# Nuio_Left_Keyboard_Rev_H_MCU.net
KiCad netlist of a schematic drawn in Altium Designer
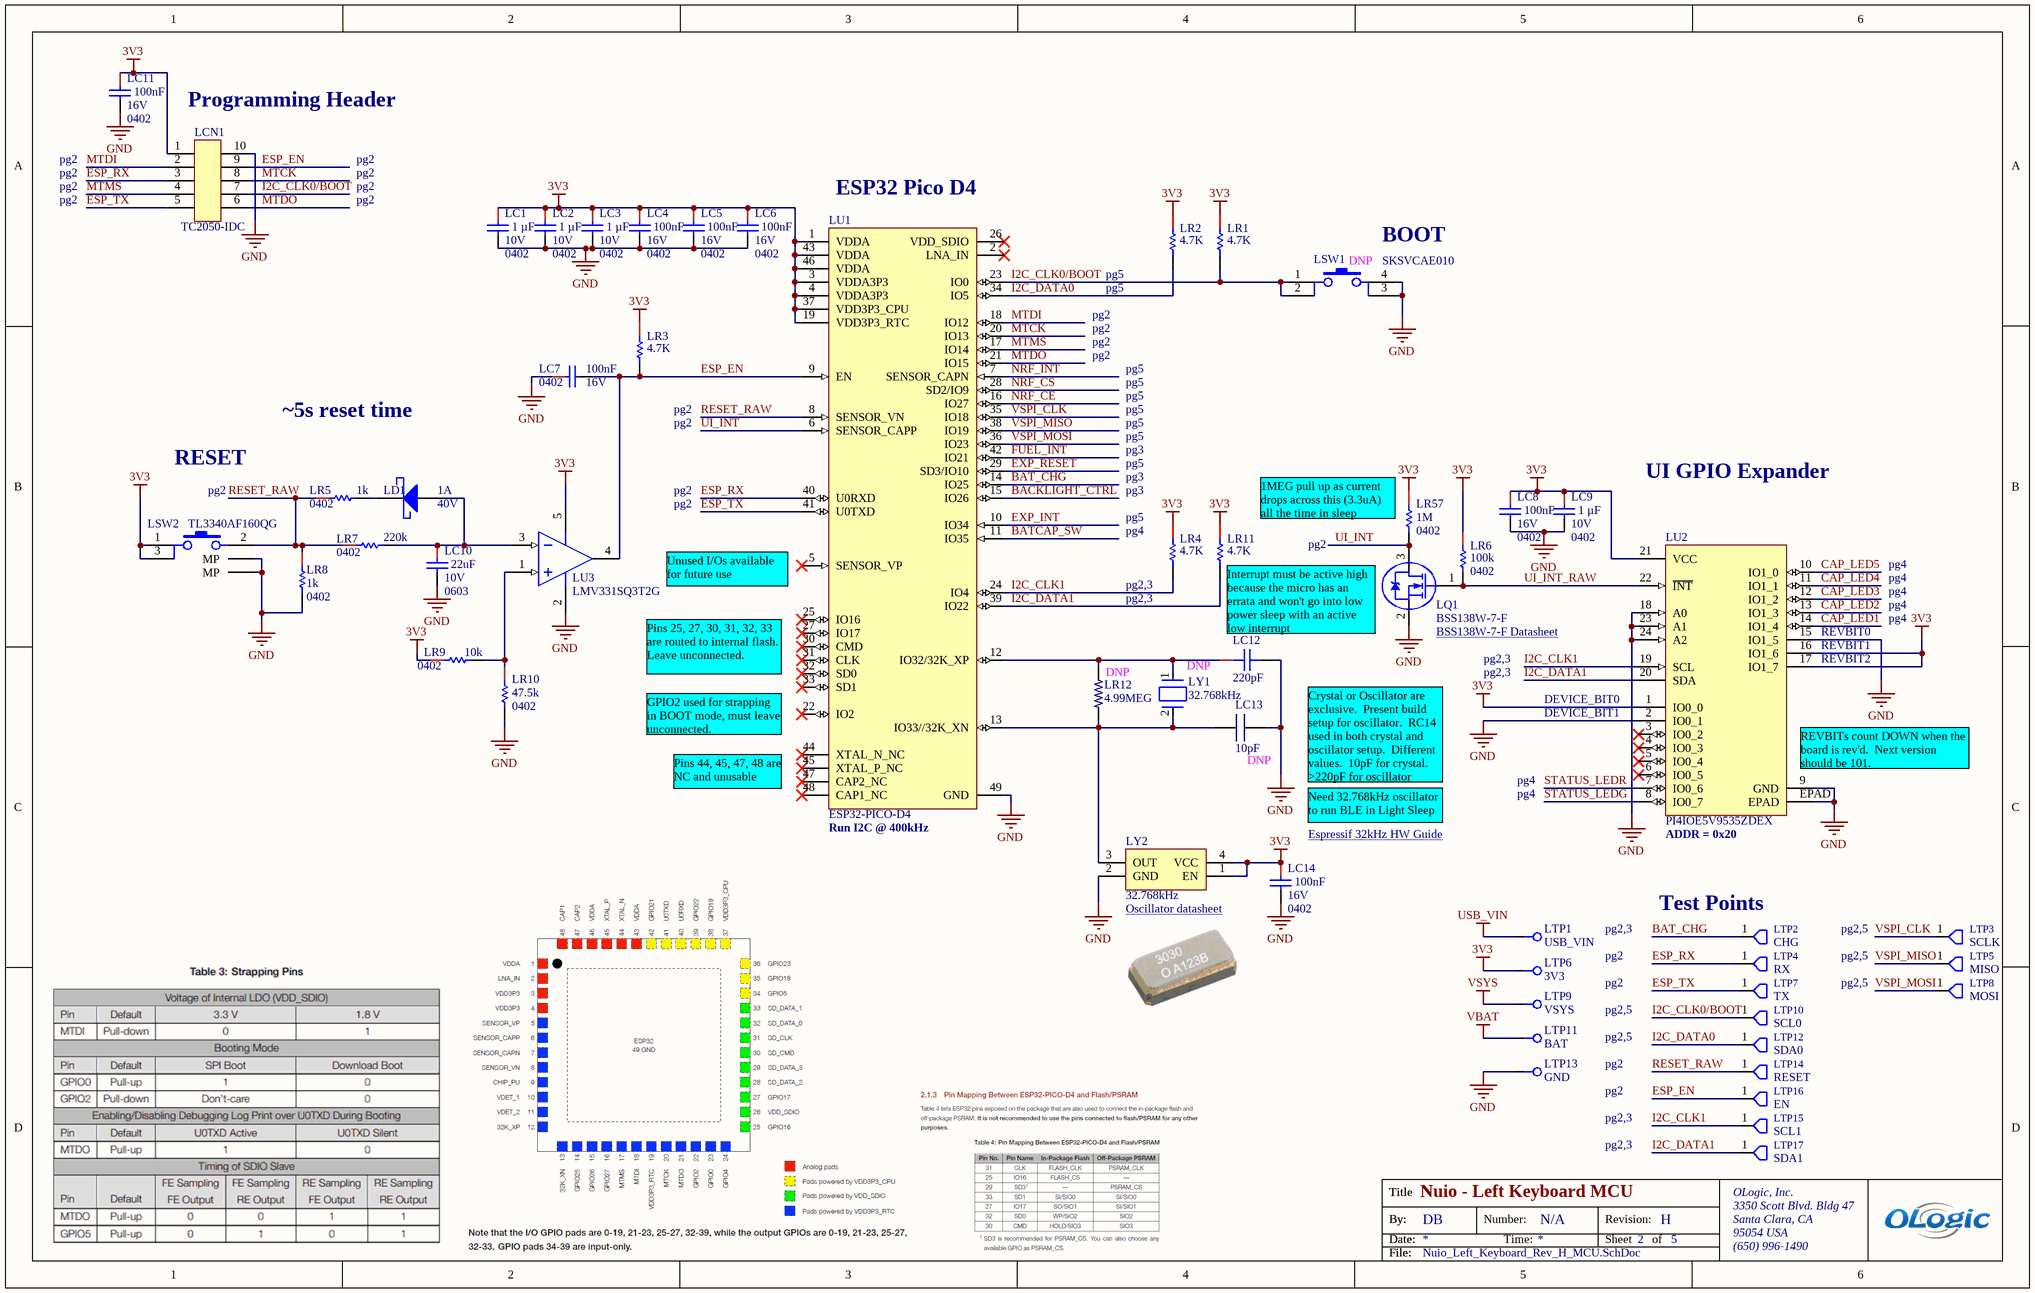
[diagram p0: Nuio_Left_Keyboard_Rev_H_MCU.SchDoc]

(export (version "E")
  (design (tool "Eeschema 10.0.6"))
  (components
    (comp (ref "LC1")
      (value "CAP CER 1UF 10V X5R 0402")
      (footprint "CAPC0402(1005)_L")
      (description "±20% 10V Ceramic Capacitor X5R 0402 (1005 Metric)")
      (fields
        (field (name "PACKAGE (IMPERIAL)") "0402")
        (field (name "VOLTAGE (RATED)") "10V")
        (field (name "CAPACITANCE") "1 µF")
        (field (name "MANUFACTURER PART NUMBER") "CC0402MRX5R6BB105")
        (field (name "TOLERANCE") "±20%")
      )
      (libsource (lib "OLogic Nexus Vault") (part "OL_Capacitor"))
    )
    (comp (ref "LC2")
      (value "CAP CER 1UF 10V X5R 0402")
      (footprint "CAPC0402(1005)_L")
      (description "±20% 10V Ceramic Capacitor X5R 0402 (1005 Metric)")
      (fields
        (field (name "PACKAGE (IMPERIAL)") "0402")
        (field (name "VOLTAGE (RATED)") "10V")
        (field (name "CAPACITANCE") "1 µF")
        (field (name "MANUFACTURER PART NUMBER") "CC0402MRX5R6BB105")
        (field (name "TOLERANCE") "±20%")
      )
      (libsource (lib "OLogic Nexus Vault") (part "OL_Capacitor"))
    )
    (comp (ref "LC3")
      (value "CAP CER 1UF 10V X5R 0402")
      (footprint "CAPC0402(1005)_L")
      (description "±20% 10V Ceramic Capacitor X5R 0402 (1005 Metric)")
      (fields
        (field (name "PACKAGE (IMPERIAL)") "0402")
        (field (name "VOLTAGE (RATED)") "10V")
        (field (name "CAPACITANCE") "1 µF")
        (field (name "MANUFACTURER PART NUMBER") "CC0402MRX5R6BB105")
        (field (name "TOLERANCE") "±20%")
      )
      (libsource (lib "OLogic Nexus Vault") (part "OL_Capacitor"))
    )
    (comp (ref "LC4")
      (value "CAP CER 0.1UF 16V X5R 0402")
      (footprint "CAPC0402(1005)_L")
      (description "±10% 16V Ceramic Capacitor X5R 0402 (1005 Metric)")
      (fields
        (field (name "PACKAGE (IMPERIAL)") "0402")
        (field (name "VOLTAGE (RATED)") "16V")
        (field (name "CAPACITANCE") "100nF")
        (field (name "MANUFACTURER") "Taiyo Yuden")
        (field (name "MANUFACTURER PART NUMBER") "EMK105BJ104KV-F")
      )
      (libsource (lib "OLogic Nexus Vault") (part "OL_Capacitor"))
    )
    (comp (ref "LC5")
      (value "CAP CER 0.1UF 16V X5R 0402")
      (footprint "CAPC0402(1005)_L")
      (description "±10% 16V Ceramic Capacitor X5R 0402 (1005 Metric)")
      (fields
        (field (name "PACKAGE (IMPERIAL)") "0402")
        (field (name "VOLTAGE (RATED)") "16V")
        (field (name "CAPACITANCE") "100nF")
        (field (name "MANUFACTURER") "Taiyo Yuden")
        (field (name "MANUFACTURER PART NUMBER") "EMK105BJ104KV-F")
      )
      (libsource (lib "OLogic Nexus Vault") (part "OL_Capacitor"))
    )
    (comp (ref "LC6")
      (value "CAP CER 0.1UF 16V X5R 0402")
      (footprint "CAPC0402(1005)_L")
      (description "±10% 16V Ceramic Capacitor X5R 0402 (1005 Metric)")
      (fields
        (field (name "PACKAGE (IMPERIAL)") "0402")
        (field (name "VOLTAGE (RATED)") "16V")
        (field (name "CAPACITANCE") "100nF")
        (field (name "MANUFACTURER") "Taiyo Yuden")
        (field (name "MANUFACTURER PART NUMBER") "EMK105BJ104KV-F")
      )
      (libsource (lib "OLogic Nexus Vault") (part "OL_Capacitor"))
    )
    (comp (ref "LC7")
      (value "CAP CER 0.1UF 16V X5R 0402")
      (footprint "CAPC0402(1005)_L")
      (description "±10% 16V Ceramic Capacitor X5R 0402 (1005 Metric)")
      (fields
        (field (name "PACKAGE (IMPERIAL)") "0402")
        (field (name "VOLTAGE (RATED)") "16V")
        (field (name "CAPACITANCE") "100nF")
        (field (name "MANUFACTURER") "Taiyo Yuden")
        (field (name "MANUFACTURER PART NUMBER") "EMK105BJ104KV-F")
      )
      (libsource (lib "OLogic Nexus Vault") (part "OL_Capacitor"))
    )
    (comp (ref "LC8")
      (value "CAP CER 0.1UF 16V X5R 0402")
      (footprint "CAPC0402(1005)_L")
      (description "±10% 16V Ceramic Capacitor X5R 0402 (1005 Metric)")
      (fields
        (field (name "PACKAGE (IMPERIAL)") "0402")
        (field (name "VOLTAGE (RATED)") "16V")
        (field (name "CAPACITANCE") "100nF")
        (field (name "MANUFACTURER") "Taiyo Yuden")
        (field (name "MANUFACTURER PART NUMBER") "EMK105BJ104KV-F")
      )
      (libsource (lib "OLogic Nexus Vault") (part "OL_Capacitor"))
    )
    (comp (ref "LC9")
      (value "CAP CER 1UF 10V X5R 0402")
      (footprint "CAPC0402(1005)_L")
      (description "±20% 10V Ceramic Capacitor X5R 0402 (1005 Metric)")
      (fields
        (field (name "PACKAGE (IMPERIAL)") "0402")
        (field (name "VOLTAGE (RATED)") "10V")
        (field (name "CAPACITANCE") "1 µF")
        (field (name "MANUFACTURER PART NUMBER") "CC0402MRX5R6BB105")
        (field (name "TOLERANCE") "±20%")
      )
      (libsource (lib "OLogic Nexus Vault") (part "OL_Capacitor"))
    )
    (comp (ref "LC10")
      (value "22uF")
      (footprint "CAPC0603(1608)_L")
      (description "CAP CER 22UF 10V 20% 0603")
      (fields
        (field (name "VOLTAGE RATING (DC)") "10V")
        (field (name "CASE CODE (IMPERIAL)") "0603")
        (field (name "TOLERANCE") "20%")
      )
      (libsource (lib "OLogic Nexus Vault") (part "=Capacitance"))
    )
    (comp (ref "LC11")
      (value "CAP CER 0.1UF 16V X5R 0402")
      (footprint "CAPC0402(1005)_L")
      (description "±10% 16V Ceramic Capacitor X5R 0402 (1005 Metric)")
      (fields
        (field (name "PACKAGE (IMPERIAL)") "0402")
        (field (name "VOLTAGE (RATED)") "16V")
        (field (name "CAPACITANCE") "100nF")
        (field (name "MANUFACTURER") "Taiyo Yuden")
        (field (name "MANUFACTURER PART NUMBER") "EMK105BJ104KV-F")
      )
      (libsource (lib "OLogic Nexus Vault") (part "OL_Capacitor"))
    )
    (comp (ref "LC12")
      (value "220pF")
      (footprint "CAPC0402(1005)_L")
      (description "220pF 25V 0402 Capacitor")
      (libsource (lib "Nuio_Left_Keyboard_Rev_H") (part "220pF"))
    )
    (comp (ref "LC13")
      (value "10pF")
      (footprint "CAPC0402(1005)_L")
      (description "10pF 16V 0402 Capacitor")
      (fields (field (name "TOLERANCE") "±10%"))
      (libsource (lib "Nuio_Left_Keyboard_Rev_G") (part "10pF 16V 0402 Capacitor"))
    )
    (comp (ref "LC14")
      (value "CAP CER 0.1UF 16V X5R 0402")
      (footprint "CAPC0402(1005)_L")
      (description "±10% 16V Ceramic Capacitor X5R 0402 (1005 Metric)")
      (fields
        (field (name "PACKAGE (IMPERIAL)") "0402")
        (field (name "VOLTAGE (RATED)") "16V")
        (field (name "CAPACITANCE") "100nF")
        (field (name "MANUFACTURER") "Taiyo Yuden")
        (field (name "MANUFACTURER PART NUMBER") "EMK105BJ104KV-F")
      )
      (libsource (lib "OLogic Nexus Vault") (part "OL_Capacitor"))
    )
    (comp (ref "LCN1")
      (value "TC2050-IDC")
      (footprint "TC2050-IDC")
      (description "Adapter Cbl Plug Of Nails 10PIN")
      (libsource (lib "Nuio_Left_Keyboard_Rev_G") (part "CMP-001-1753-01"))
    )
    (comp (ref "LD1")
      (value "PMEG4010AESBYL")
      (footprint "PMEG4010AESBYL-Footprint-1")
      (description "DIODE SCHOTTKY 40V 1A SOD993")
      (fields (field (name "DC REVERSE VOLTAGE MAX") "40V") (field (name "CURRENT AVG RECTIFIED") "1A"))
      (libsource (lib "OLogic Nexus Vault") (part "PMEG4010AESB"))
    )
    (comp (ref "LQ1")
      (value "BSS138W-7-F")
      (footprint "DIOD-SOT323-3_V")
      (description "DIODES INC. - BSS138W-7-F. - BSS FAMILY SOT323 T&R 3K ROHS COMPLIANT: YES")
      (fields (field (name "VOLTAGE") "50V") (field (name "POWER") "200mW"))
      (libsource (lib "Nuio_Left_Keyboard_Rev_H") (part "CMP-00300-01"))
    )
    (comp (ref "LR1")
      (value "4.7K")
      (footprint "RESC0402(1005)_L")
      (description "SMD Chip Resistor, 4.7 kOhm, ± 1%, 62.5 mW, 0402 [1005 Metric], Thick Film, General Purpose")
      (fields (field (name "TOLERANCE") "1%"))
      (libsource (lib "Nuio_Left_Keyboard_Rev_G") (part "CMP-001-0724-07"))
    )
    (comp (ref "LR2")
      (value "4.7K")
      (footprint "RESC0402(1005)_L")
      (description "SMD Chip Resistor, 4.7 kOhm, ± 1%, 62.5 mW, 0402 [1005 Metric], Thick Film, General Purpose")
      (fields (field (name "TOLERANCE") "1%"))
      (libsource (lib "Nuio_Left_Keyboard_Rev_G") (part "CMP-001-0724-07"))
    )
    (comp (ref "LR3")
      (value "4.7K")
      (footprint "RESC0402(1005)_L")
      (description "SMD Chip Resistor, 4.7 kOhm, ± 1%, 62.5 mW, 0402 [1005 Metric], Thick Film, General Purpose")
      (fields (field (name "TOLERANCE") "1%"))
      (libsource (lib "Nuio_Left_Keyboard_Rev_G") (part "CMP-001-0724-07"))
    )
    (comp (ref "LR4")
      (value "4.7K")
      (footprint "RESC0402(1005)_L")
      (description "SMD Chip Resistor, 4.7 kOhm, ± 1%, 62.5 mW, 0402 [1005 Metric], Thick Film, General Purpose")
      (fields (field (name "TOLERANCE") "1%"))
      (libsource (lib "Nuio_Left_Keyboard_Rev_G") (part "CMP-001-0724-07"))
    )
    (comp (ref "LR5")
      (value "RES SMD 1K OHM 1% 1/16W 0402")
      (footprint "RESC0402(1005)_L")
      (fields
        (field (name "RESISTANCE") "1k")
        (field (name "PACKAGE (IMPERIAL)") "0402")
        (field (name "POWER") "63mW")
        (field (name "MANUFACTURER") "Yageo")
        (field (name "TOLERANCE") "1%")
      )
      (libsource (lib "OLogic Nexus Vault") (part "OL_Resistor"))
    )
    (comp (ref "LR6")
      (value "100k")
      (footprint "RESC0402(1005)_L")
      (description "±1% 0.063W, 1/16W Chip Resistor 0402 (1005 Metric) Moisture Resistant Thick Film")
      (fields
        (field (name "CASE CODE (IMPERIAL)") "0402")
        (field (name "TOLERANCE") "1%")
        (field (name "MANUFACTURER") "YAGEO")
      )
      (libsource (lib "OLogic Nexus Vault") (part "=Resistance"))
    )
    (comp (ref "LR7")
      (value "220K")
      (footprint "RESC0402(1005)_L")
      (description "RES SMD 220K OHM 1% 1/10W 0402")
      (fields
        (field (name "PACKAGE (IMPERIAL)") "0402")
        (field (name "RESISTANCE") "220k")
        (field (name "TOLERANCE") "1%")
        (field (name "POWER") "63mW")
      )
      (libsource (lib "OLogic Nexus Vault") (part "=Resistance"))
    )
    (comp (ref "LR8")
      (value "RES SMD 1K OHM 1% 1/16W 0402")
      (footprint "RESC0402(1005)_L")
      (fields
        (field (name "RESISTANCE") "1k")
        (field (name "PACKAGE (IMPERIAL)") "0402")
        (field (name "POWER") "63mW")
        (field (name "MANUFACTURER") "Yageo")
        (field (name "TOLERANCE") "1%")
      )
      (libsource (lib "OLogic Nexus Vault") (part "OL_Resistor"))
    )
    (comp (ref "LR9")
      (value "RES SMD 10K OHM 1% 1/16W 0402")
      (footprint "RESC0402_YAGEO")
      (fields
        (field (name "RESISTANCE") "10k")
        (field (name "PACKAGE (IMPERIAL)") "0402")
        (field (name "MANUFACTURER") "Yageo")
        (field (name "TOLERANCE") "1%")
        (field (name "MANUFACTURER PART NUMBER") "AT0402FRE0710KL")
      )
      (libsource (lib "OLogic Nexus Vault") (part "OL_Resistor"))
    )
    (comp (ref "LR10")
      (value "RES 47.5K OHM 1% 1/16W 0402")
      (footprint "RESC0402(1005)_L")
      (description "47.5 kOhms ±1% 0.063W, 1/16W Chip Resistor 0402 (1005 Metric) Moisture Resistant Thick Film")
      (fields
        (field (name "RESISTANCE") "47.5k")
        (field (name "PACKAGE (IMPERIAL)") "0402")
        (field (name "MANUFACTURER") "Panasonic Electronic Components")
        (field (name "MANUFACTURER PART NUMBER") "ERA-2ARB6041X")
      )
      (libsource (lib "OLogic Nexus Vault") (part "OL_Resistor"))
    )
    (comp (ref "LR11")
      (value "4.7K")
      (footprint "RESC0402(1005)_L")
      (description "SMD Chip Resistor, 4.7 kOhm, ± 1%, 62.5 mW, 0402 [1005 Metric], Thick Film, General Purpose")
      (fields (field (name "TOLERANCE") "1%"))
      (libsource (lib "Nuio_Left_Keyboard_Rev_G") (part "CMP-001-0724-07"))
    )
    (comp (ref "LR12")
      (value "4.99MEG")
      (footprint "RESC0402(1005)_L")
      (description "4.99MEG 0402 Resistor 1%")
      (fields
        (field (name "MANUFACTURER") "Vishay Dale")
        (field (name "MANUFACTURER PART NUMBER") "CRCW04024M99FKEDC")
      )
      (libsource (lib "Nuio_Left_Keyboard_Rev_G") (part "4.99MEG 0402 Resistor 1%"))
    )
    (comp (ref "LR57")
      (value "RES 1M OHM 1% 1/16W 0402")
      (footprint "RESC0402(1005)_L")
      (description "1 MOhms ±1% 0.063W, 1/16W Chip Resistor 0402 (1005 Metric) Moisture Resistant Thick Film")
      (fields
        (field (name "RESISTANCE") "1M")
        (field (name "CASE/PACKAGE") "0402")
        (field (name "MANUFACTURER") "YAGEO")
        (field (name "MANUFACTURER PART NUMBER") "RC0402FR-071ML")
      )
      (libsource (lib "OLogic Nexus Vault") (part "OL_Resistor"))
    )
    (comp (ref "LSW1")
      (value "SKSVCAE010")
      (footprint "SKSVCAE010")
      (description "2.8x1.9mm Compact Type with Projection Surface Mount SKSV Series Tact Switch")
      (fields (field (name "MANUFACTURER") "Alps Alpine"))
      (libsource (lib "OLogic Nexus Vault") (part "OL_Switch_Tactile_4"))
    )
    (comp (ref "LSW2")
      (value "TL3340AF160QG")
      (footprint "TL3340AF160QG")
      (description "SWITCH TACTILE SPST-NO 0.05A 12V")
      (libsource (lib "OLogic Nexus Vault") (part "TL3340AF160QG"))
    )
    (comp (ref "LTP1")
      (value "USB_VIN")
      (footprint "Pogo-Testpoint")
      (description "Test Point- Current one")
      (libsource (lib "OLogic Nexus Vault") (part "TestPoint"))
    )
    (comp (ref "LTP2")
      (value "CHG")
      (footprint "MTK-TESTPOINT-20")
      (description "MTK-TP20MIL")
      (libsource (lib "OLogic Nexus Vault") (part "MTK-TESTPOINT-20"))
    )
    (comp (ref "LTP3")
      (value "SCLK")
      (footprint "MTK-TESTPOINT-20")
      (description "MTK-TP20MIL")
      (libsource (lib "OLogic Nexus Vault") (part "MTK-TESTPOINT-20"))
    )
    (comp (ref "LTP4")
      (value "RX")
      (footprint "MTK-TESTPOINT-20")
      (description "MTK-TP20MIL")
      (libsource (lib "OLogic Nexus Vault") (part "MTK-TESTPOINT-20"))
    )
    (comp (ref "LTP5")
      (value "MISO")
      (footprint "MTK-TESTPOINT-20")
      (description "MTK-TP20MIL")
      (libsource (lib "OLogic Nexus Vault") (part "MTK-TESTPOINT-20"))
    )
    (comp (ref "LTP6")
      (value "3V3")
      (footprint "Pogo-Testpoint")
      (description "Test Point- Current one")
      (libsource (lib "OLogic Nexus Vault") (part "TestPoint"))
    )
    (comp (ref "LTP7")
      (value "TX")
      (footprint "MTK-TESTPOINT-20")
      (description "MTK-TP20MIL")
      (libsource (lib "OLogic Nexus Vault") (part "MTK-TESTPOINT-20"))
    )
    (comp (ref "LTP8")
      (value "MOSI")
      (footprint "MTK-TESTPOINT-20")
      (description "MTK-TP20MIL")
      (libsource (lib "OLogic Nexus Vault") (part "MTK-TESTPOINT-20"))
    )
    (comp (ref "LTP9")
      (value "VSYS")
      (footprint "Pogo-Testpoint")
      (description "Test Point- Current one")
      (libsource (lib "OLogic Nexus Vault") (part "TestPoint"))
    )
    (comp (ref "LTP10")
      (value "SCL0")
      (footprint "MTK-TESTPOINT-20")
      (description "MTK-TP20MIL")
      (libsource (lib "OLogic Nexus Vault") (part "MTK-TESTPOINT-20"))
    )
    (comp (ref "LTP11")
      (value "BAT")
      (footprint "Pogo-Testpoint")
      (description "Test Point- Current one")
      (libsource (lib "OLogic Nexus Vault") (part "TestPoint"))
    )
    (comp (ref "LTP12")
      (value "SDA0")
      (footprint "MTK-TESTPOINT-20")
      (description "MTK-TP20MIL")
      (libsource (lib "Nuio_Left_Keyboard_Rev_G") (part "CMP-001-1043-02"))
    )
    (comp (ref "LTP13")
      (value "GND")
      (footprint "Pogo-Testpoint")
      (description "Test Point- Current one")
      (libsource (lib "OLogic Nexus Vault") (part "TestPoint"))
    )
    (comp (ref "LTP14")
      (value "RESET")
      (footprint "MTK-TESTPOINT-20")
      (description "MTK-TP20MIL")
      (libsource (lib "OLogic Nexus Vault") (part "MTK-TESTPOINT-20"))
    )
    (comp (ref "LTP15")
      (value "SCL1")
      (footprint "MTK-TESTPOINT-20")
      (description "MTK-TP20MIL")
      (libsource (lib "Nuio_Left_Keyboard_Rev_G") (part "CMP-001-1043-02"))
    )
    (comp (ref "LTP16")
      (value "EN")
      (footprint "MTK-TESTPOINT-20")
      (description "MTK-TP20MIL")
      (libsource (lib "OLogic Nexus Vault") (part "MTK-TESTPOINT-20"))
    )
    (comp (ref "LTP17")
      (value "SDA1")
      (footprint "MTK-TESTPOINT-20")
      (description "MTK-TP20MIL")
      (libsource (lib "Nuio_Left_Keyboard_Rev_G") (part "CMP-001-1043-02"))
    )
    (comp (ref "LU1")
      (value "ESP32-PICO-D4")
      (footprint "ESP32-PICO-D4")
      (description "SoC RF SIP Module Dual Core MCU 2, 4GHz")
      (libsource (lib "Nuio_Left_Keyboard_Rev_G") (part "CMP-001-1982-03"))
    )
    (comp (ref "LU2")
      (value "PI4IOE5V9535ZDEX")
      (footprint "PI4IOE5V9535ZDEX")
      (description "IC I/o Expander 16B I2C 24TQFN")
      (libsource (lib "Nuio_Left_Keyboard_Rev_G") (part "CMP-001-2127-03"))
    )
    (comp (ref "LU3")
      (value "LMV331SQ3T2G")
      (footprint "ONSC-SC70-5-419A-02_K_L")
      (description "LMV Series 5 V 1 nA SMT Single General Purpose, Low Voltage Comparator - SC-70")
      (fields (field (name "MANUFACTURER") "onsemi"))
      (libsource (lib "OLogic Nexus Vault") (part "ONSC-LMV331-5"))
    )
    (comp (ref "LY1")
      (value "32.768kHz")
      (footprint "FP-9HT10-MFG")
      (description "CRYSTAL 32.7680KHZ 6PF SMD")
      (libsource (lib "Altium Content Vault") (part "c23a69dc6c9e2f18f2079038eb95dd1"))
    )
    (comp (ref "LY2")
      (value "32.768kHz")
      (footprint "Nuio_Left_Keyboard_Rev_H:ESPSON SG-3031CM")
      (description "Crystal Oscillator, Surface Mount Type")
      (libsource (lib "Nuio_Left_Keyboard_Rev_H") (part "OSCILLATOR SG-3031CM 32.7680KB0"))
    )
  )
  (nets
    (net (code "1") (name "/BACKLIGHT_CTRL") (class "Default")
      (node (ref "LU1") (pin "15") (pinfunction "IO26_15") (pintype "bidirectional"))
    )
    (net (code "2") (name "/BATCAP_SW") (class "Default")
      (node (ref "LU1") (pin "11") (pinfunction "IO35_11") (pintype "input"))
    )
    (net (code "3") (name "/BAT_CHG") (class "Default")
      (node (ref "LTP2") (pin "1") (pinfunction "TP_1") (pintype "passive"))
      (node (ref "LU1") (pin "14") (pinfunction "IO25_14") (pintype "bidirectional"))
    )
    (net (code "4") (name "/CAP_LED1") (class "Default")
      (node (ref "LU2") (pin "14") (pinfunction "IO1_4_14") (pintype "bidirectional"))
    )
    (net (code "5") (name "/CAP_LED2") (class "Default")
      (node (ref "LU2") (pin "13") (pinfunction "IO1_3_13") (pintype "bidirectional"))
    )
    (net (code "6") (name "/CAP_LED3") (class "Default")
      (node (ref "LU2") (pin "12") (pinfunction "IO1_2_12") (pintype "bidirectional"))
    )
    (net (code "7") (name "/CAP_LED4") (class "Default")
      (node (ref "LU2") (pin "11") (pinfunction "IO1_1_11") (pintype "bidirectional"))
    )
    (net (code "8") (name "/CAP_LED5") (class "Default")
      (node (ref "LU2") (pin "10") (pinfunction "IO1_0_10") (pintype "bidirectional"))
    )
    (net (code "9") (name "/ESP_EN") (class "Default")
      (node (ref "LC7") (pin "2") (pinfunction "2_2") (pintype "passive"))
      (node (ref "LCN1") (pin "9") (pintype "passive"))
      (node (ref "LR3") (pin "2") (pinfunction "2_2") (pintype "passive"))
      (node (ref "LTP16") (pin "1") (pinfunction "TP_1") (pintype "passive"))
      (node (ref "LU1") (pin "9") (pinfunction "EN_9") (pintype "input"))
      (node (ref "LU3") (pin "4") (pinfunction "OUT_4") (pintype "open_collector"))
    )
    (net (code "10") (name "/ESP_RX") (class "Default")
      (node (ref "LCN1") (pin "3") (pintype "passive"))
      (node (ref "LTP4") (pin "1") (pinfunction "TP_1") (pintype "passive"))
      (node (ref "LU1") (pin "40") (pinfunction "U0RXD_40") (pintype "bidirectional"))
    )
    (net (code "11") (name "/ESP_TX") (class "Default")
      (node (ref "LCN1") (pin "5") (pintype "passive"))
      (node (ref "LTP7") (pin "1") (pinfunction "TP_1") (pintype "passive"))
      (node (ref "LU1") (pin "41") (pinfunction "U0TXD_41") (pintype "bidirectional"))
    )
    (net (code "12") (name "/EXP_INT") (class "Default")
      (node (ref "LU1") (pin "10") (pinfunction "IO34_10") (pintype "input"))
    )
    (net (code "13") (name "/EXP_RESET") (class "Default")
      (node (ref "LU1") (pin "29") (pinfunction "SD3/IO10_29") (pintype "bidirectional"))
    )
    (net (code "14") (name "/FUEL_INT") (class "Default")
      (node (ref "LU1") (pin "42") (pinfunction "IO21_42") (pintype "bidirectional"))
    )
    (net (code "15") (name "/I2C_CLK0{slash}BOOT") (class "Default")
      (node (ref "LCN1") (pin "7") (pintype "passive"))
      (node (ref "LR1") (pin "2") (pinfunction "2_2") (pintype "passive"))
      (node (ref "LSW1") (pin "1") (pinfunction "1_1") (pintype "passive"))
      (node (ref "LSW1") (pin "2") (pinfunction "2_2") (pintype "passive"))
      (node (ref "LTP10") (pin "1") (pinfunction "TP_1") (pintype "passive"))
      (node (ref "LU1") (pin "23") (pinfunction "IO0_23") (pintype "bidirectional"))
    )
    (net (code "16") (name "/I2C_CLK1") (class "Default")
      (node (ref "LR4") (pin "2") (pinfunction "2_2") (pintype "passive"))
      (node (ref "LTP15") (pin "1") (pinfunction "TP_1") (pintype "passive"))
      (node (ref "LU1") (pin "24") (pinfunction "IO4_24") (pintype "bidirectional"))
      (node (ref "LU2") (pin "19") (pinfunction "SCL_19") (pintype "input"))
    )
    (net (code "17") (name "/I2C_DATA0") (class "Default")
      (node (ref "LR2") (pin "2") (pinfunction "2_2") (pintype "passive"))
      (node (ref "LTP12") (pin "1") (pinfunction "TP_1") (pintype "passive"))
      (node (ref "LU1") (pin "34") (pinfunction "IO5_34") (pintype "bidirectional"))
    )
    (net (code "18") (name "/I2C_DATA1") (class "Default")
      (node (ref "LR11") (pin "2") (pinfunction "2_2") (pintype "passive"))
      (node (ref "LTP17") (pin "1") (pinfunction "TP_1") (pintype "passive"))
      (node (ref "LU1") (pin "39") (pinfunction "IO22_39") (pintype "bidirectional"))
      (node (ref "LU2") (pin "20") (pinfunction "SDA_20") (pintype "passive"))
    )
    (net (code "19") (name "/MTCK") (class "Default")
      (node (ref "LCN1") (pin "8") (pintype "passive"))
      (node (ref "LU1") (pin "20") (pinfunction "IO13_20") (pintype "bidirectional"))
    )
    (net (code "20") (name "/MTDI") (class "Default")
      (node (ref "LCN1") (pin "2") (pintype "passive"))
      (node (ref "LU1") (pin "18") (pinfunction "IO12_18") (pintype "bidirectional"))
    )
    (net (code "21") (name "/MTDO") (class "Default")
      (node (ref "LCN1") (pin "6") (pintype "passive"))
      (node (ref "LU1") (pin "21") (pinfunction "IO15_21") (pintype "bidirectional"))
    )
    (net (code "22") (name "/MTMS") (class "Default")
      (node (ref "LCN1") (pin "4") (pintype "passive"))
      (node (ref "LU1") (pin "17") (pinfunction "IO14_17") (pintype "bidirectional"))
    )
    (net (code "23") (name "/NRF_CE") (class "Default")
      (node (ref "LU1") (pin "16") (pinfunction "IO27_16") (pintype "bidirectional"))
    )
    (net (code "24") (name "/NRF_CS") (class "Default")
      (node (ref "LU1") (pin "28") (pinfunction "SD2/IO9_28") (pintype "bidirectional"))
    )
    (net (code "25") (name "/NRF_INT") (class "Default")
      (node (ref "LU1") (pin "7") (pinfunction "SENSOR_CAPN_7") (pintype "input"))
    )
    (net (code "26") (name "/RESET_RAW") (class "Default")
      (node (ref "LR5") (pin "1") (pinfunction "1_1") (pintype "passive"))
      (node (ref "LR7") (pin "1") (pinfunction "1_1") (pintype "passive"))
      (node (ref "LR8") (pin "1") (pinfunction "1_1") (pintype "passive"))
      (node (ref "LSW2") (pin "2") (pinfunction "2_2") (pintype "passive"))
      (node (ref "LTP14") (pin "1") (pinfunction "TP_1") (pintype "passive"))
      (node (ref "LU1") (pin "8") (pinfunction "SENSOR_VN_8") (pintype "input"))
    )
    (net (code "27") (name "/STATUS_LEDG") (class "Default")
      (node (ref "LU2") (pin "8") (pinfunction "IO0_7_8") (pintype "bidirectional"))
    )
    (net (code "28") (name "/STATUS_LEDR") (class "Default")
      (node (ref "LU2") (pin "7") (pinfunction "IO0_6_7") (pintype "bidirectional"))
    )
    (net (code "29") (name "/UI_INT") (class "Default")
      (node (ref "LQ1") (pin "3") (pinfunction "D_3") (pintype "passive"))
      (node (ref "LR57") (pin "2") (pinfunction "2_2") (pintype "passive"))
      (node (ref "LU1") (pin "6") (pinfunction "SENSOR_CAPP_6") (pintype "input"))
    )
    (net (code "30") (name "/UI_INT_RAW") (class "Default")
      (node (ref "LQ1") (pin "1") (pinfunction "G_1") (pintype "passive"))
      (node (ref "LR6") (pin "2") (pinfunction "2_2") (pintype "passive"))
      (node (ref "LU2") (pin "22") (pinfunction "~{INT}_22") (pintype "input"))
    )
    (net (code "31") (name "/VSPI_CLK") (class "Default")
      (node (ref "LTP3") (pin "1") (pinfunction "TP_1") (pintype "passive"))
      (node (ref "LU1") (pin "35") (pinfunction "IO18_35") (pintype "bidirectional"))
    )
    (net (code "32") (name "/VSPI_MISO") (class "Default")
      (node (ref "LTP5") (pin "1") (pinfunction "TP_1") (pintype "passive"))
      (node (ref "LU1") (pin "38") (pinfunction "IO19_38") (pintype "bidirectional"))
    )
    (net (code "33") (name "/VSPI_MOSI") (class "Default")
      (node (ref "LTP8") (pin "1") (pinfunction "TP_1") (pintype "passive"))
      (node (ref "LU1") (pin "36") (pinfunction "IO23_36") (pintype "bidirectional"))
    )
    (net (code "34") (name "3V3") (class "Default")
      (node (ref "LC1") (pin "1") (pinfunction "1_1") (pintype "passive"))
      (node (ref "LC11") (pin "1") (pinfunction "1_1") (pintype "passive"))
      (node (ref "LC14") (pin "1") (pinfunction "1_1") (pintype "passive"))
      (node (ref "LC2") (pin "1") (pinfunction "1_1") (pintype "passive"))
      (node (ref "LC3") (pin "1") (pinfunction "1_1") (pintype "passive"))
      (node (ref "LC4") (pin "1") (pinfunction "1_1") (pintype "passive"))
      (node (ref "LC5") (pin "1") (pinfunction "1_1") (pintype "passive"))
      (node (ref "LC6") (pin "1") (pinfunction "1_1") (pintype "passive"))
      (node (ref "LC8") (pin "1") (pinfunction "1_1") (pintype "passive"))
      (node (ref "LC9") (pin "1") (pinfunction "1_1") (pintype "passive"))
      (node (ref "LCN1") (pin "1") (pintype "passive"))
      (node (ref "LR1") (pin "1") (pinfunction "1_1") (pintype "passive"))
      (node (ref "LR11") (pin "1") (pinfunction "1_1") (pintype "passive"))
      (node (ref "LR2") (pin "1") (pinfunction "1_1") (pintype "passive"))
      (node (ref "LR3") (pin "1") (pinfunction "1_1") (pintype "passive"))
      (node (ref "LR4") (pin "1") (pinfunction "1_1") (pintype "passive"))
      (node (ref "LR57") (pin "1") (pinfunction "1_1") (pintype "passive"))
      (node (ref "LR6") (pin "1") (pinfunction "1_1") (pintype "passive"))
      (node (ref "LR9") (pin "1") (pinfunction "1_1") (pintype "passive"))
      (node (ref "LSW2") (pin "1") (pinfunction "1_1") (pintype "passive"))
      (node (ref "LSW2") (pin "3") (pinfunction "3_3") (pintype "passive"))
      (node (ref "LTP6") (pin "1") (pinfunction "1_1") (pintype "passive"))
      (node (ref "LU1") (pin "1") (pinfunction "VDDA_1") (pintype "power_in"))
      (node (ref "LU1") (pin "19") (pinfunction "VDD3P3_RTC_19") (pintype "passive"))
      (node (ref "LU1") (pin "3") (pinfunction "VDDA3P3_3") (pintype "power_in"))
      (node (ref "LU1") (pin "37") (pinfunction "VDD3P3_CPU_37") (pintype "power_in"))
      (node (ref "LU1") (pin "4") (pinfunction "VDDA3P3_4") (pintype "power_in"))
      (node (ref "LU1") (pin "43") (pinfunction "VDDA_43") (pintype "power_in"))
      (node (ref "LU1") (pin "46") (pinfunction "VDDA_46") (pintype "power_in"))
      (node (ref "LU2") (pin "1") (pinfunction "IO0_0_1") (pintype "passive"))
      (node (ref "LU2") (pin "16") (pinfunction "IO1_6_16") (pintype "passive"))
      (node (ref "LU2") (pin "17") (pinfunction "IO1_7_17") (pintype "passive"))
      (node (ref "LU2") (pin "21") (pinfunction "VCC_21") (pintype "passive"))
      (node (ref "LU3") (pin "5") (pinfunction "VCC_5") (pintype "power_in"))
      (node (ref "LY2") (pin "1") (pinfunction "EN_1") (pintype "passive"))
      (node (ref "LY2") (pin "4") (pinfunction "VCC_4") (pintype "passive"))
    )
    (net (code "35") (name "GND") (class "Default")
      (node (ref "LC1") (pin "2") (pinfunction "2_2") (pintype "passive"))
      (node (ref "LC10") (pin "2") (pinfunction "2_2") (pintype "passive"))
      (node (ref "LC11") (pin "2") (pinfunction "2_2") (pintype "passive"))
      (node (ref "LC12") (pin "2") (pinfunction "2_2") (pintype "passive"))
      (node (ref "LC13") (pin "2") (pinfunction "2_2") (pintype "passive"))
      (node (ref "LC14") (pin "2") (pinfunction "2_2") (pintype "passive"))
      (node (ref "LC2") (pin "2") (pinfunction "2_2") (pintype "passive"))
      (node (ref "LC3") (pin "2") (pinfunction "2_2") (pintype "passive"))
      (node (ref "LC4") (pin "2") (pinfunction "2_2") (pintype "passive"))
      (node (ref "LC5") (pin "2") (pinfunction "2_2") (pintype "passive"))
      (node (ref "LC6") (pin "2") (pinfunction "2_2") (pintype "passive"))
      (node (ref "LC7") (pin "1") (pinfunction "1_1") (pintype "passive"))
      (node (ref "LC8") (pin "2") (pinfunction "2_2") (pintype "passive"))
      (node (ref "LC9") (pin "2") (pinfunction "2_2") (pintype "passive"))
      (node (ref "LCN1") (pin "10") (pintype "passive"))
      (node (ref "LQ1") (pin "2") (pinfunction "S_2") (pintype "passive"))
      (node (ref "LR10") (pin "2") (pinfunction "2_2") (pintype "passive"))
      (node (ref "LR8") (pin "2") (pinfunction "2_2") (pintype "passive"))
      (node (ref "LSW1") (pin "3") (pinfunction "3_3") (pintype "passive"))
      (node (ref "LSW1") (pin "4") (pinfunction "4_4") (pintype "passive"))
      (node (ref "LSW2") (pin "MP1") (pinfunction "MP_MP1") (pintype "passive"))
      (node (ref "LSW2") (pin "MP2") (pinfunction "MP_MP2") (pintype "passive"))
      (node (ref "LTP13") (pin "1") (pinfunction "1_1") (pintype "passive"))
      (node (ref "LU1") (pin "49") (pinfunction "GND_49") (pintype "power_in"))
      (node (ref "LU2") (pin "15") (pinfunction "IO1_5_15") (pintype "passive"))
      (node (ref "LU2") (pin "18") (pinfunction "A0_18") (pintype "input"))
      (node (ref "LU2") (pin "2") (pinfunction "IO0_1_2") (pintype "passive"))
      (node (ref "LU2") (pin "23") (pinfunction "A1_23") (pintype "input"))
      (node (ref "LU2") (pin "24") (pinfunction "A2_24") (pintype "input"))
      (node (ref "LU2") (pin "9") (pinfunction "GND_9") (pintype "passive"))
      (node (ref "LU2") (pin "EPAD") (pinfunction "EPAD_EPAD") (pintype "passive"))
      (node (ref "LU3") (pin "2") (pinfunction "GND_2") (pintype "power_in"))
      (node (ref "LY2") (pin "2") (pinfunction "GND_2") (pintype "passive"))
    )
    (net (code "36") (name "Net-(LD1-A)") (class "Default")
      (node (ref "LC10") (pin "1") (pinfunction "1_1") (pintype "passive"))
      (node (ref "LD1") (pin "2") (pinfunction "A_2") (pintype "passive"))
      (node (ref "LR7") (pin "2") (pinfunction "2_2") (pintype "passive"))
      (node (ref "LU3") (pin "3") (pinfunction "IN-_3") (pintype "input"))
    )
    (net (code "37") (name "Net-(LD1-K)") (class "Default")
      (node (ref "LD1") (pin "1") (pinfunction "K_1") (pintype "passive"))
      (node (ref "LR5") (pin "2") (pinfunction "2_2") (pintype "passive"))
    )
    (net (code "38") (name "Net-(LU1-IO32{slash}32K_XP)") (class "Default")
      (node (ref "LC12") (pin "1") (pinfunction "1_1") (pintype "passive"))
      (node (ref "LR12") (pin "2") (pinfunction "2_2") (pintype "passive"))
      (node (ref "LU1") (pin "12") (pinfunction "IO32/32K_XP_12") (pintype "bidirectional"))
      (node (ref "LY1") (pin "1") (pinfunction "1_1") (pintype "passive"))
    )
    (net (code "39") (name "Net-(LU1-IO33{slash}{slash}32K_XN)") (class "Default")
      (node (ref "LC13") (pin "1") (pinfunction "1_1") (pintype "passive"))
      (node (ref "LR12") (pin "1") (pinfunction "1_1") (pintype "passive"))
      (node (ref "LU1") (pin "13") (pinfunction "IO33//32K_XN_13") (pintype "bidirectional"))
      (node (ref "LY1") (pin "2") (pinfunction "2_2") (pintype "passive"))
      (node (ref "LY2") (pin "3") (pinfunction "OUT_3") (pintype "passive"))
    )
    (net (code "40") (name "Net-(LU3-IN+)") (class "Default")
      (node (ref "LR10") (pin "1") (pinfunction "1_1") (pintype "passive"))
      (node (ref "LR9") (pin "2") (pinfunction "2_2") (pintype "passive"))
      (node (ref "LU3") (pin "1") (pinfunction "IN+_1") (pintype "input"))
    )
    (net (code "41") (name "USB_VIN") (class "Default")
      (node (ref "LTP1") (pin "1") (pinfunction "1_1") (pintype "passive"))
    )
    (net (code "42") (name "VBAT") (class "Default")
      (node (ref "LTP11") (pin "1") (pinfunction "1_1") (pintype "passive"))
    )
    (net (code "43") (name "VSYS") (class "Default")
      (node (ref "LTP9") (pin "1") (pinfunction "1_1") (pintype "passive"))
    )
    (net (code "44") (name "unconnected-(LU1-CAP1_NC-Pad48)") (class "Default")
      (node (ref "LU1") (pin "48") (pinfunction "CAP1_NC_48") (pintype "passive+no_connect"))
    )
    (net (code "45") (name "unconnected-(LU1-CAP2_NC-Pad47)") (class "Default")
      (node (ref "LU1") (pin "47") (pinfunction "CAP2_NC_47") (pintype "passive+no_connect"))
    )
    (net (code "46") (name "unconnected-(LU1-CLK-Pad31)") (class "Default")
      (node (ref "LU1") (pin "31") (pinfunction "CLK_31") (pintype "bidirectional+no_connect"))
    )
    (net (code "47") (name "unconnected-(LU1-CMD-Pad30)") (class "Default")
      (node (ref "LU1") (pin "30") (pinfunction "CMD_30") (pintype "bidirectional+no_connect"))
    )
    (net (code "48") (name "unconnected-(LU1-IO2-Pad22)") (class "Default")
      (node (ref "LU1") (pin "22") (pinfunction "IO2_22") (pintype "bidirectional+no_connect"))
    )
    (net (code "49") (name "unconnected-(LU1-IO16-Pad25)") (class "Default")
      (node (ref "LU1") (pin "25") (pinfunction "IO16_25") (pintype "bidirectional+no_connect"))
    )
    (net (code "50") (name "unconnected-(LU1-IO17-Pad27)") (class "Default")
      (node (ref "LU1") (pin "27") (pinfunction "IO17_27") (pintype "bidirectional+no_connect"))
    )
    (net (code "51") (name "unconnected-(LU1-LNA_IN-Pad2)") (class "Default")
      (node (ref "LU1") (pin "2") (pinfunction "LNA_IN_2") (pintype "passive+no_connect"))
    )
    (net (code "52") (name "unconnected-(LU1-SD0-Pad32)") (class "Default")
      (node (ref "LU1") (pin "32") (pinfunction "SD0_32") (pintype "bidirectional+no_connect"))
    )
    (net (code "53") (name "unconnected-(LU1-SD1-Pad33)") (class "Default")
      (node (ref "LU1") (pin "33") (pinfunction "SD1_33") (pintype "bidirectional+no_connect"))
    )
    (net (code "54") (name "unconnected-(LU1-SENSOR_VP-Pad5)") (class "Default")
      (node (ref "LU1") (pin "5") (pinfunction "SENSOR_VP_5") (pintype "input+no_connect"))
    )
    (net (code "55") (name "unconnected-(LU1-VDD_SDIO-Pad26)") (class "Default")
      (node (ref "LU1") (pin "26") (pinfunction "VDD_SDIO_26") (pintype "power_in+no_connect"))
    )
    (net (code "56") (name "unconnected-(LU1-XTAL_N_NC-Pad44)") (class "Default")
      (node (ref "LU1") (pin "44") (pinfunction "XTAL_N_NC_44") (pintype "passive+no_connect"))
    )
    (net (code "57") (name "unconnected-(LU1-XTAL_P_NC-Pad45)") (class "Default")
      (node (ref "LU1") (pin "45") (pinfunction "XTAL_P_NC_45") (pintype "passive+no_connect"))
    )
    (net (code "58") (name "unconnected-(LU2-IO0_2-Pad3)") (class "Default")
      (node (ref "LU2") (pin "3") (pinfunction "IO0_2_3") (pintype "bidirectional+no_connect"))
    )
    (net (code "59") (name "unconnected-(LU2-IO0_3-Pad4)") (class "Default")
      (node (ref "LU2") (pin "4") (pinfunction "IO0_3_4") (pintype "bidirectional+no_connect"))
    )
    (net (code "60") (name "unconnected-(LU2-IO0_4-Pad5)") (class "Default")
      (node (ref "LU2") (pin "5") (pinfunction "IO0_4_5") (pintype "bidirectional+no_connect"))
    )
    (net (code "61") (name "unconnected-(LU2-IO0_5-Pad6)") (class "Default")
      (node (ref "LU2") (pin "6") (pinfunction "IO0_5_6") (pintype "bidirectional+no_connect"))
    )
  )
)
